# ModuleBtnMatrix25sw.net
KiCad netlist of a schematic drawn in EasyEDA Pro
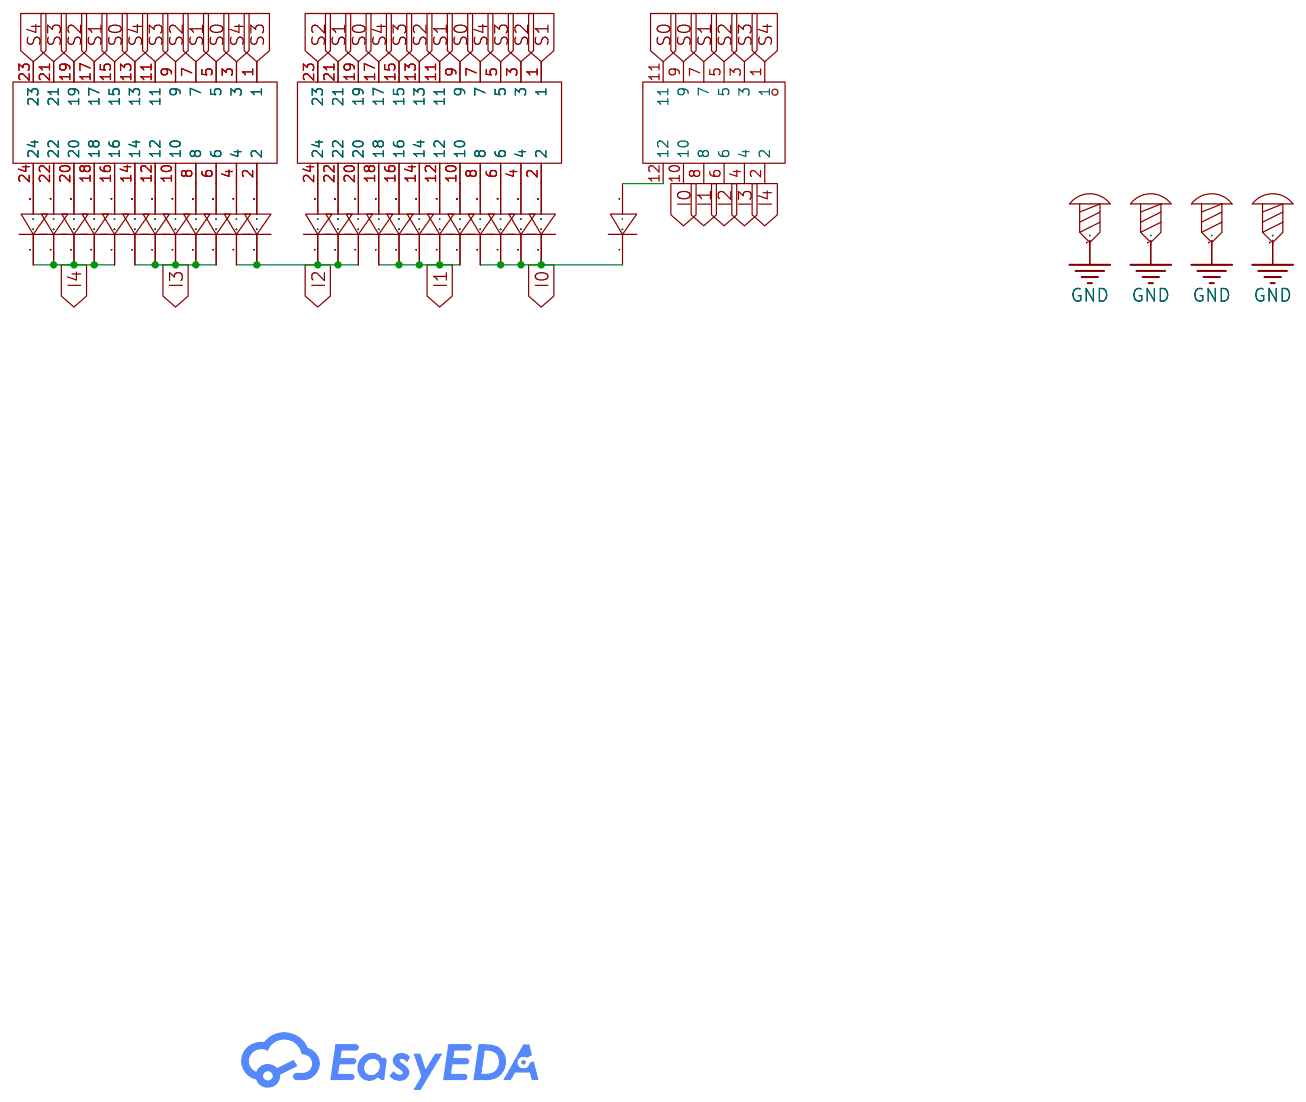
[diagram p0: schematic sheet]

(export (version "E")
  (design (tool "Eeschema 10.0.6"))
  (components
    (comp (ref "D1")
      (value "1N4148")
      (footprint "easyedapro:DO-35_BD2.0-L4.2-P8.20-D0.5-RD")
      (fields (field (name "Manufacturer") "LGE(鲁光)"))
      (libsource (lib "easyedapro") (part "1N4148_C402212"))
    )
    (comp (ref "D14")
      (value "1N4148")
      (footprint "easyedapro:DO-35_BD2.0-L4.2-P8.20-D0.5-RD")
      (fields (field (name "Manufacturer") "LGE(鲁光)"))
      (libsource (lib "easyedapro") (part "1N4148_C402212"))
    )
    (comp (ref "D15")
      (value "1N4148")
      (footprint "easyedapro:DO-35_BD2.0-L4.2-P8.20-D0.5-RD")
      (fields (field (name "Manufacturer") "LGE(鲁光)"))
      (libsource (lib "easyedapro") (part "1N4148_C402212"))
    )
    (comp (ref "D16")
      (value "1N4148")
      (footprint "easyedapro:DO-35_BD2.0-L4.2-P8.20-D0.5-RD")
      (fields (field (name "Manufacturer") "LGE(鲁光)"))
      (libsource (lib "easyedapro") (part "1N4148_C402212"))
    )
    (comp (ref "D17")
      (value "1N4148")
      (footprint "easyedapro:DO-35_BD2.0-L4.2-P8.20-D0.5-RD")
      (fields (field (name "Manufacturer") "LGE(鲁光)"))
      (libsource (lib "easyedapro") (part "1N4148_C402212"))
    )
    (comp (ref "D18")
      (value "1N4148")
      (footprint "easyedapro:DO-35_BD2.0-L4.2-P8.20-D0.5-RD")
      (fields (field (name "Manufacturer") "LGE(鲁光)"))
      (libsource (lib "easyedapro") (part "1N4148_C402212"))
    )
    (comp (ref "D19")
      (value "1N4148")
      (footprint "easyedapro:DO-35_BD2.0-L4.2-P8.20-D0.5-RD")
      (fields (field (name "Manufacturer") "LGE(鲁光)"))
      (libsource (lib "easyedapro") (part "1N4148_C402212"))
    )
    (comp (ref "D20")
      (value "1N4148")
      (footprint "easyedapro:DO-35_BD2.0-L4.2-P8.20-D0.5-RD")
      (fields (field (name "Manufacturer") "LGE(鲁光)"))
      (libsource (lib "easyedapro") (part "1N4148_C402212"))
    )
    (comp (ref "D21")
      (value "1N4148")
      (footprint "easyedapro:DO-35_BD2.0-L4.2-P8.20-D0.5-RD")
      (fields (field (name "Manufacturer") "LGE(鲁光)"))
      (libsource (lib "easyedapro") (part "1N4148_C402212"))
    )
    (comp (ref "D22")
      (value "1N4148")
      (footprint "easyedapro:DO-35_BD2.0-L4.2-P8.20-D0.5-RD")
      (fields (field (name "Manufacturer") "LGE(鲁光)"))
      (libsource (lib "easyedapro") (part "1N4148_C402212"))
    )
    (comp (ref "D23")
      (value "1N4148")
      (footprint "easyedapro:DO-35_BD2.0-L4.2-P8.20-D0.5-RD")
      (fields (field (name "Manufacturer") "LGE(鲁光)"))
      (libsource (lib "easyedapro") (part "1N4148_C402212"))
    )
    (comp (ref "D24")
      (value "1N4148")
      (footprint "easyedapro:DO-35_BD2.0-L4.2-P8.20-D0.5-RD")
      (fields (field (name "Manufacturer") "LGE(鲁光)"))
      (libsource (lib "easyedapro") (part "1N4148_C402212"))
    )
    (comp (ref "D25")
      (value "1N4148")
      (footprint "easyedapro:DO-35_BD2.0-L4.2-P8.20-D0.5-RD")
      (fields (field (name "Manufacturer") "LGE(鲁光)"))
      (libsource (lib "easyedapro") (part "1N4148_C402212"))
    )
    (comp (ref "D26")
      (value "1N4148")
      (footprint "easyedapro:DO-35_BD2.0-L4.2-P8.20-D0.5-RD")
      (fields (field (name "Manufacturer") "LGE(鲁光)"))
      (libsource (lib "easyedapro") (part "1N4148_C402212"))
    )
    (comp (ref "D27")
      (value "1N4148")
      (footprint "easyedapro:DO-35_BD2.0-L4.2-P8.20-D0.5-RD")
      (fields (field (name "Manufacturer") "LGE(鲁光)"))
      (libsource (lib "easyedapro") (part "1N4148_C402212"))
    )
    (comp (ref "D28")
      (value "1N4148")
      (footprint "easyedapro:DO-35_BD2.0-L4.2-P8.20-D0.5-RD")
      (fields (field (name "Manufacturer") "LGE(鲁光)"))
      (libsource (lib "easyedapro") (part "1N4148_C402212"))
    )
    (comp (ref "D29")
      (value "1N4148")
      (footprint "easyedapro:DO-35_BD2.0-L4.2-P8.20-D0.5-RD")
      (fields (field (name "Manufacturer") "LGE(鲁光)"))
      (libsource (lib "easyedapro") (part "1N4148_C402212"))
    )
    (comp (ref "D30")
      (value "1N4148")
      (footprint "easyedapro:DO-35_BD2.0-L4.2-P8.20-D0.5-RD")
      (fields (field (name "Manufacturer") "LGE(鲁光)"))
      (libsource (lib "easyedapro") (part "1N4148_C402212"))
    )
    (comp (ref "D31")
      (value "1N4148")
      (footprint "easyedapro:DO-35_BD2.0-L4.2-P8.20-D0.5-RD")
      (fields (field (name "Manufacturer") "LGE(鲁光)"))
      (libsource (lib "easyedapro") (part "1N4148_C402212"))
    )
    (comp (ref "D32")
      (value "1N4148")
      (footprint "easyedapro:DO-35_BD2.0-L4.2-P8.20-D0.5-RD")
      (fields (field (name "Manufacturer") "LGE(鲁光)"))
      (libsource (lib "easyedapro") (part "1N4148_C402212"))
    )
    (comp (ref "D33")
      (value "1N4148")
      (footprint "easyedapro:DO-35_BD2.0-L4.2-P8.20-D0.5-RD")
      (fields (field (name "Manufacturer") "LGE(鲁光)"))
      (libsource (lib "easyedapro") (part "1N4148_C402212"))
    )
    (comp (ref "D34")
      (value "1N4148")
      (footprint "easyedapro:DO-35_BD2.0-L4.2-P8.20-D0.5-RD")
      (fields (field (name "Manufacturer") "LGE(鲁光)"))
      (libsource (lib "easyedapro") (part "1N4148_C402212"))
    )
    (comp (ref "D35")
      (value "1N4148")
      (footprint "easyedapro:DO-35_BD2.0-L4.2-P8.20-D0.5-RD")
      (fields (field (name "Manufacturer") "LGE(鲁光)"))
      (libsource (lib "easyedapro") (part "1N4148_C402212"))
    )
    (comp (ref "D36")
      (value "1N4148")
      (footprint "easyedapro:DO-35_BD2.0-L4.2-P8.20-D0.5-RD")
      (fields (field (name "Manufacturer") "LGE(鲁光)"))
      (libsource (lib "easyedapro") (part "1N4148_C402212"))
    )
    (comp (ref "D37")
      (value "1N4148")
      (footprint "easyedapro:DO-35_BD2.0-L4.2-P8.20-D0.5-RD")
      (fields (field (name "Manufacturer") "LGE(鲁光)"))
      (libsource (lib "easyedapro") (part "1N4148_C402212"))
    )
    (comp (ref "SCREW1")
      (value "~")
      (footprint "easyedapro:Screw-Hole-M2")
      (libsource (lib "easyedapro") (part "Screw-Hole"))
    )
    (comp (ref "SCREW2")
      (value "~")
      (footprint "easyedapro:Screw-Hole-M2")
      (libsource (lib "easyedapro") (part "Screw-Hole"))
    )
    (comp (ref "SCREW3")
      (value "~")
      (footprint "easyedapro:Screw-Hole-M2")
      (libsource (lib "easyedapro") (part "Screw-Hole"))
    )
    (comp (ref "SCREW4")
      (value "~")
      (footprint "easyedapro:Screw-Hole-M2")
      (libsource (lib "easyedapro") (part "Screw-Hole"))
    )
    (comp (ref "U1")
      (value "2541WR-2x12P")
      (footprint "easyedapro:HDR-TH_24P-P2.54-H-M-R2-C12-S2.54-N")
      (fields (field (name "Manufacturer") "HanElectricity(瀚源)"))
      (libsource (lib "easyedapro") (part "2541WR-2X12P"))
    )
    (comp (ref "U2")
      (value "2541WR-2x12P")
      (footprint "easyedapro:HDR-TH_24P-P2.54-H-M-R2-C12-S2.54-N")
      (fields (field (name "Manufacturer") "HanElectricity(瀚源)"))
      (libsource (lib "easyedapro") (part "2541WR-2X12P"))
    )
    (comp (ref "U4")
      (value "2541WR-2x06P")
      (footprint "easyedapro:HDR-TH_12P-P2.54-H-M-R2-C6-S2.54-N")
      (fields (field (name "Manufacturer") "HanElectricity(瀚源)"))
      (libsource (lib "easyedapro") (part "2541WR-2X06P"))
    )
  )
  (nets
    (net (code "1") (name "GND") (class "Default")
      (node (ref "SCREW1") (pin "1") (pinfunction "1_1") (pintype "input"))
      (node (ref "SCREW2") (pin "1") (pinfunction "1_1") (pintype "input"))
      (node (ref "SCREW3") (pin "1") (pinfunction "1_1") (pintype "input"))
      (node (ref "SCREW4") (pin "1") (pinfunction "1_1") (pintype "input"))
    )
    (net (code "2") (name "I0") (class "Default")
      (node (ref "D33") (pin "1") (pinfunction "C_1") (pintype "unspecified"))
      (node (ref "D34") (pin "1") (pinfunction "C_1") (pintype "unspecified"))
      (node (ref "D35") (pin "1") (pinfunction "C_1") (pintype "unspecified"))
      (node (ref "D36") (pin "1") (pinfunction "C_1") (pintype "unspecified"))
      (node (ref "D37") (pin "1") (pinfunction "C_1") (pintype "unspecified"))
      (node (ref "U4") (pin "10") (pinfunction "10_10") (pintype "unspecified"))
    )
    (net (code "3") (name "I1") (class "Default")
      (node (ref "D28") (pin "1") (pinfunction "C_1") (pintype "unspecified"))
      (node (ref "D29") (pin "1") (pinfunction "C_1") (pintype "unspecified"))
      (node (ref "D30") (pin "1") (pinfunction "C_1") (pintype "unspecified"))
      (node (ref "D31") (pin "1") (pinfunction "C_1") (pintype "unspecified"))
      (node (ref "D32") (pin "1") (pinfunction "C_1") (pintype "unspecified"))
      (node (ref "U4") (pin "8") (pinfunction "8_8") (pintype "unspecified"))
    )
    (net (code "4") (name "I2") (class "Default")
      (node (ref "D23") (pin "1") (pinfunction "C_1") (pintype "unspecified"))
      (node (ref "D24") (pin "1") (pinfunction "C_1") (pintype "unspecified"))
      (node (ref "D25") (pin "1") (pinfunction "C_1") (pintype "unspecified"))
      (node (ref "D26") (pin "1") (pinfunction "C_1") (pintype "unspecified"))
      (node (ref "D27") (pin "1") (pinfunction "C_1") (pintype "unspecified"))
      (node (ref "U4") (pin "6") (pinfunction "6_6") (pintype "unspecified"))
    )
    (net (code "5") (name "I3") (class "Default")
      (node (ref "D18") (pin "1") (pinfunction "C_1") (pintype "unspecified"))
      (node (ref "D19") (pin "1") (pinfunction "C_1") (pintype "unspecified"))
      (node (ref "D20") (pin "1") (pinfunction "C_1") (pintype "unspecified"))
      (node (ref "D21") (pin "1") (pinfunction "C_1") (pintype "unspecified"))
      (node (ref "D22") (pin "1") (pinfunction "C_1") (pintype "unspecified"))
      (node (ref "U4") (pin "4") (pinfunction "4_4") (pintype "unspecified"))
    )
    (net (code "6") (name "I4") (class "Default")
      (node (ref "D1") (pin "1") (pinfunction "C_1") (pintype "unspecified"))
      (node (ref "D14") (pin "1") (pinfunction "C_1") (pintype "unspecified"))
      (node (ref "D15") (pin "1") (pinfunction "C_1") (pintype "unspecified"))
      (node (ref "D16") (pin "1") (pinfunction "C_1") (pintype "unspecified"))
      (node (ref "D17") (pin "1") (pinfunction "C_1") (pintype "unspecified"))
      (node (ref "U4") (pin "2") (pinfunction "2_2") (pintype "unspecified"))
    )
    (net (code "7") (name "Net-(D1-A)") (class "Default")
      (node (ref "D1") (pin "2") (pinfunction "A_2") (pintype "unspecified"))
      (node (ref "U1") (pin "24") (pinfunction "24_24") (pintype "unspecified"))
    )
    (net (code "8") (name "Net-(D14-A)") (class "Default")
      (node (ref "D14") (pin "2") (pinfunction "A_2") (pintype "unspecified"))
      (node (ref "U1") (pin "22") (pinfunction "22_22") (pintype "unspecified"))
    )
    (net (code "9") (name "Net-(D15-A)") (class "Default")
      (node (ref "D15") (pin "2") (pinfunction "A_2") (pintype "unspecified"))
      (node (ref "U1") (pin "20") (pinfunction "20_20") (pintype "unspecified"))
    )
    (net (code "10") (name "Net-(D16-A)") (class "Default")
      (node (ref "D16") (pin "2") (pinfunction "A_2") (pintype "unspecified"))
      (node (ref "U1") (pin "18") (pinfunction "18_18") (pintype "unspecified"))
    )
    (net (code "11") (name "Net-(D17-A)") (class "Default")
      (node (ref "D17") (pin "2") (pinfunction "A_2") (pintype "unspecified"))
      (node (ref "U1") (pin "16") (pinfunction "16_16") (pintype "unspecified"))
    )
    (net (code "12") (name "Net-(D18-A)") (class "Default")
      (node (ref "D18") (pin "2") (pinfunction "A_2") (pintype "unspecified"))
      (node (ref "U1") (pin "14") (pinfunction "14_14") (pintype "unspecified"))
    )
    (net (code "13") (name "Net-(D19-A)") (class "Default")
      (node (ref "D19") (pin "2") (pinfunction "A_2") (pintype "unspecified"))
      (node (ref "U1") (pin "12") (pinfunction "12_12") (pintype "unspecified"))
    )
    (net (code "14") (name "Net-(D20-A)") (class "Default")
      (node (ref "D20") (pin "2") (pinfunction "A_2") (pintype "unspecified"))
      (node (ref "U1") (pin "10") (pinfunction "10_10") (pintype "unspecified"))
    )
    (net (code "15") (name "Net-(D21-A)") (class "Default")
      (node (ref "D21") (pin "2") (pinfunction "A_2") (pintype "unspecified"))
      (node (ref "U1") (pin "8") (pinfunction "8_8") (pintype "unspecified"))
    )
    (net (code "16") (name "Net-(D22-A)") (class "Default")
      (node (ref "D22") (pin "2") (pinfunction "A_2") (pintype "unspecified"))
      (node (ref "U1") (pin "6") (pinfunction "6_6") (pintype "unspecified"))
    )
    (net (code "17") (name "Net-(D23-A)") (class "Default")
      (node (ref "D23") (pin "2") (pinfunction "A_2") (pintype "unspecified"))
      (node (ref "U1") (pin "4") (pinfunction "4_4") (pintype "unspecified"))
    )
    (net (code "18") (name "Net-(D24-A)") (class "Default")
      (node (ref "D24") (pin "2") (pinfunction "A_2") (pintype "unspecified"))
      (node (ref "U1") (pin "2") (pinfunction "2_2") (pintype "unspecified"))
    )
    (net (code "19") (name "Net-(D25-A)") (class "Default")
      (node (ref "D25") (pin "2") (pinfunction "A_2") (pintype "unspecified"))
      (node (ref "U2") (pin "24") (pinfunction "24_24") (pintype "unspecified"))
    )
    (net (code "20") (name "Net-(D26-A)") (class "Default")
      (node (ref "D26") (pin "2") (pinfunction "A_2") (pintype "unspecified"))
      (node (ref "U2") (pin "22") (pinfunction "22_22") (pintype "unspecified"))
    )
    (net (code "21") (name "Net-(D27-A)") (class "Default")
      (node (ref "D27") (pin "2") (pinfunction "A_2") (pintype "unspecified"))
      (node (ref "U2") (pin "20") (pinfunction "20_20") (pintype "unspecified"))
    )
    (net (code "22") (name "Net-(D28-A)") (class "Default")
      (node (ref "D28") (pin "2") (pinfunction "A_2") (pintype "unspecified"))
      (node (ref "U2") (pin "18") (pinfunction "18_18") (pintype "unspecified"))
    )
    (net (code "23") (name "Net-(D29-A)") (class "Default")
      (node (ref "D29") (pin "2") (pinfunction "A_2") (pintype "unspecified"))
      (node (ref "U2") (pin "16") (pinfunction "16_16") (pintype "unspecified"))
    )
    (net (code "24") (name "Net-(D30-A)") (class "Default")
      (node (ref "D30") (pin "2") (pinfunction "A_2") (pintype "unspecified"))
      (node (ref "U2") (pin "14") (pinfunction "14_14") (pintype "unspecified"))
    )
    (net (code "25") (name "Net-(D31-A)") (class "Default")
      (node (ref "D31") (pin "2") (pinfunction "A_2") (pintype "unspecified"))
      (node (ref "U2") (pin "12") (pinfunction "12_12") (pintype "unspecified"))
    )
    (net (code "26") (name "Net-(D32-A)") (class "Default")
      (node (ref "D32") (pin "2") (pinfunction "A_2") (pintype "unspecified"))
      (node (ref "U2") (pin "10") (pinfunction "10_10") (pintype "unspecified"))
    )
    (net (code "27") (name "Net-(D33-A)") (class "Default")
      (node (ref "D33") (pin "2") (pinfunction "A_2") (pintype "unspecified"))
      (node (ref "U2") (pin "8") (pinfunction "8_8") (pintype "unspecified"))
    )
    (net (code "28") (name "Net-(D34-A)") (class "Default")
      (node (ref "D34") (pin "2") (pinfunction "A_2") (pintype "unspecified"))
      (node (ref "U2") (pin "6") (pinfunction "6_6") (pintype "unspecified"))
    )
    (net (code "29") (name "Net-(D35-A)") (class "Default")
      (node (ref "D35") (pin "2") (pinfunction "A_2") (pintype "unspecified"))
      (node (ref "U2") (pin "4") (pinfunction "4_4") (pintype "unspecified"))
    )
    (net (code "30") (name "Net-(D36-A)") (class "Default")
      (node (ref "D36") (pin "2") (pinfunction "A_2") (pintype "unspecified"))
      (node (ref "U2") (pin "2") (pinfunction "2_2") (pintype "unspecified"))
    )
    (net (code "31") (name "Net-(D37-A)") (class "Default")
      (node (ref "D37") (pin "2") (pinfunction "A_2") (pintype "unspecified"))
      (node (ref "U4") (pin "12") (pinfunction "12_12") (pintype "unspecified"))
    )
    (net (code "32") (name "S0") (class "Default")
      (node (ref "U1") (pin "15") (pinfunction "15_15") (pintype "unspecified"))
      (node (ref "U1") (pin "5") (pinfunction "5_5") (pintype "unspecified"))
      (node (ref "U2") (pin "19") (pinfunction "19_19") (pintype "unspecified"))
      (node (ref "U2") (pin "9") (pinfunction "9_9") (pintype "unspecified"))
      (node (ref "U4") (pin "11") (pinfunction "11_11") (pintype "unspecified"))
      (node (ref "U4") (pin "9") (pinfunction "9_9") (pintype "unspecified"))
    )
    (net (code "33") (name "S1") (class "Default")
      (node (ref "U1") (pin "17") (pinfunction "17_17") (pintype "unspecified"))
      (node (ref "U1") (pin "7") (pinfunction "7_7") (pintype "unspecified"))
      (node (ref "U2") (pin "1") (pinfunction "1_1") (pintype "unspecified"))
      (node (ref "U2") (pin "11") (pinfunction "11_11") (pintype "unspecified"))
      (node (ref "U2") (pin "21") (pinfunction "21_21") (pintype "unspecified"))
      (node (ref "U4") (pin "7") (pinfunction "7_7") (pintype "unspecified"))
    )
    (net (code "34") (name "S2") (class "Default")
      (node (ref "U1") (pin "19") (pinfunction "19_19") (pintype "unspecified"))
      (node (ref "U1") (pin "9") (pinfunction "9_9") (pintype "unspecified"))
      (node (ref "U2") (pin "13") (pinfunction "13_13") (pintype "unspecified"))
      (node (ref "U2") (pin "23") (pinfunction "23_23") (pintype "unspecified"))
      (node (ref "U2") (pin "3") (pinfunction "3_3") (pintype "unspecified"))
      (node (ref "U4") (pin "5") (pinfunction "5_5") (pintype "unspecified"))
    )
    (net (code "35") (name "S3") (class "Default")
      (node (ref "U1") (pin "1") (pinfunction "1_1") (pintype "unspecified"))
      (node (ref "U1") (pin "11") (pinfunction "11_11") (pintype "unspecified"))
      (node (ref "U1") (pin "21") (pinfunction "21_21") (pintype "unspecified"))
      (node (ref "U2") (pin "15") (pinfunction "15_15") (pintype "unspecified"))
      (node (ref "U2") (pin "5") (pinfunction "5_5") (pintype "unspecified"))
      (node (ref "U4") (pin "3") (pinfunction "3_3") (pintype "unspecified"))
    )
    (net (code "36") (name "S4") (class "Default")
      (node (ref "U1") (pin "13") (pinfunction "13_13") (pintype "unspecified"))
      (node (ref "U1") (pin "23") (pinfunction "23_23") (pintype "unspecified"))
      (node (ref "U1") (pin "3") (pinfunction "3_3") (pintype "unspecified"))
      (node (ref "U2") (pin "17") (pinfunction "17_17") (pintype "unspecified"))
      (node (ref "U2") (pin "7") (pinfunction "7_7") (pintype "unspecified"))
      (node (ref "U4") (pin "1") (pinfunction "1_1") (pintype "unspecified"))
    )
  )
)
